# Dual_filter_common_mode_and_differential.net
KiCad netlist of a schematic drawn in EAGLE
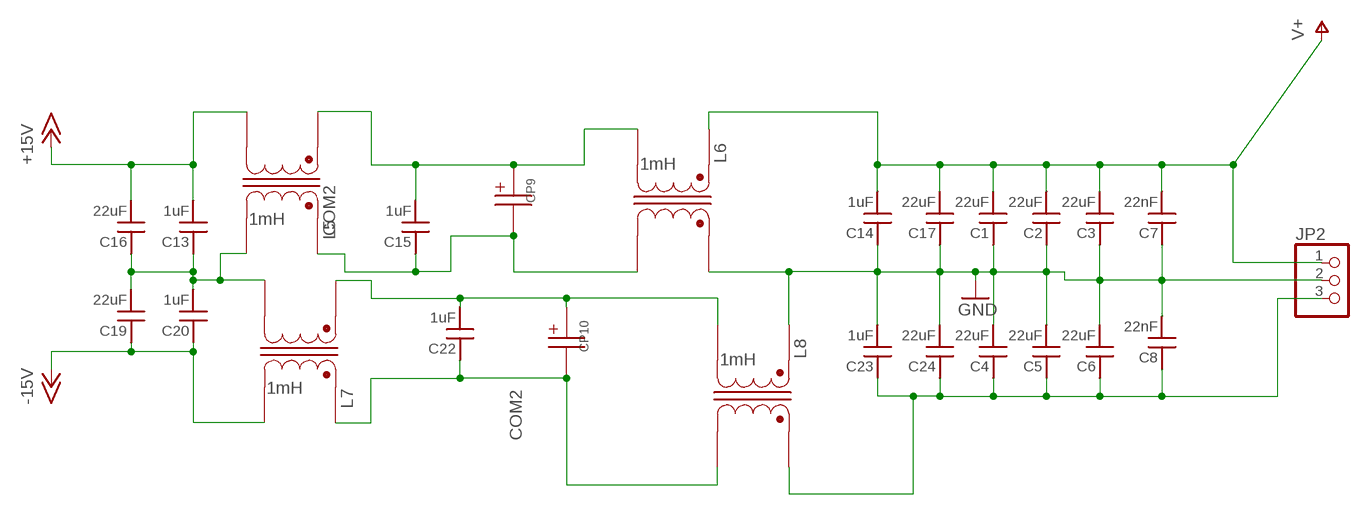
[diagram p0: schematic, sheet 1]

(export (version "E")
  (design (tool "Eeschema 10.0.6"))
  (components
    (comp (ref "C1")
      (value "22uF")
      (footprint "eagle-import:C_MLCC_0805")
      (libsource (lib "eagle-import") (part "C_MLCC_SMDCMLCC_0805"))
    )
    (comp (ref "C2")
      (value "22uF")
      (footprint "eagle-import:C_MLCC_0805")
      (libsource (lib "eagle-import") (part "C_MLCC_SMDCMLCC_0805"))
    )
    (comp (ref "C3")
      (value "22uF")
      (footprint "eagle-import:C_MLCC_0805")
      (libsource (lib "eagle-import") (part "C_MLCC_SMDCMLCC_0805"))
    )
    (comp (ref "C4")
      (value "22uF")
      (footprint "eagle-import:C_MLCC_0805")
      (libsource (lib "eagle-import") (part "C_MLCC_SMDCMLCC_0805"))
    )
    (comp (ref "C5")
      (value "22uF")
      (footprint "eagle-import:C_MLCC_0805")
      (libsource (lib "eagle-import") (part "C_MLCC_SMDCMLCC_0805"))
    )
    (comp (ref "C6")
      (value "22uF")
      (footprint "eagle-import:C_MLCC_0805")
      (libsource (lib "eagle-import") (part "C_MLCC_SMDCMLCC_0805"))
    )
    (comp (ref "C7")
      (value "22nF")
      (footprint "eagle-import:C_MLCC_0306")
      (libsource (lib "eagle-import") (part "C_MLCC_SMDCMLCC_0306"))
    )
    (comp (ref "C8")
      (value "22nF")
      (footprint "eagle-import:C_MLCC_0306")
      (libsource (lib "eagle-import") (part "C_MLCC_SMDCMLCC_0306"))
    )
    (comp (ref "C13")
      (value "1uF")
      (footprint "eagle-import:C_MLCC_0805")
      (libsource (lib "eagle-import") (part "C_MLCC_SMDCMLCC_0805"))
    )
    (comp (ref "C14")
      (value "1uF")
      (footprint "eagle-import:C_MLCC_0805")
      (libsource (lib "eagle-import") (part "C_MLCC_SMDCMLCC_0805"))
    )
    (comp (ref "C15")
      (value "1uF")
      (footprint "eagle-import:C_MLCC_0805")
      (libsource (lib "eagle-import") (part "C_MLCC_SMDCMLCC_0805"))
    )
    (comp (ref "C16")
      (value "22uF")
      (footprint "eagle-import:C_MLCC_0805")
      (libsource (lib "eagle-import") (part "C_MLCC_SMDCMLCC_0805"))
    )
    (comp (ref "C17")
      (value "22uF")
      (footprint "eagle-import:C_MLCC_0805")
      (libsource (lib "eagle-import") (part "C_MLCC_SMDCMLCC_0805"))
    )
    (comp (ref "C19")
      (value "22uF")
      (footprint "eagle-import:C_MLCC_0805")
      (libsource (lib "eagle-import") (part "C_MLCC_SMDCMLCC_0805"))
    )
    (comp (ref "C20")
      (value "1uF")
      (footprint "eagle-import:C_MLCC_0805")
      (libsource (lib "eagle-import") (part "C_MLCC_SMDCMLCC_0805"))
    )
    (comp (ref "C22")
      (value "1uF")
      (footprint "eagle-import:C_MLCC_0805")
      (libsource (lib "eagle-import") (part "C_MLCC_SMDCMLCC_0805"))
    )
    (comp (ref "C23")
      (value "1uF")
      (footprint "eagle-import:C_MLCC_0805")
      (libsource (lib "eagle-import") (part "C_MLCC_SMDCMLCC_0805"))
    )
    (comp (ref "C24")
      (value "22uF")
      (footprint "eagle-import:C_MLCC_0805")
      (libsource (lib "eagle-import") (part "C_MLCC_SMDCMLCC_0805"))
    )
    (comp (ref "CP9")
      (value "CAP-POLPANASONIC_F")
      (footprint "eagle-import:PANASONIC_F")
      (libsource (lib "eagle-import") (part "CAP-POLPANASONIC_F"))
    )
    (comp (ref "CP10")
      (value "CAP-POLPANASONIC_F")
      (footprint "eagle-import:PANASONIC_F")
      (libsource (lib "eagle-import") (part "CAP-POLPANASONIC_F"))
    )
    (comp (ref "JP2")
      (value "PINHD-1X3")
      (footprint "eagle-import:1X03")
      (libsource (lib "eagle-import") (part "PINHD-1X3"))
    )
    (comp (ref "L5")
      (value "1mH")
      (footprint "eagle-import:COILCRAFT_TRANSFORMER_MSD1260")
      (libsource (lib "eagle-import") (part "COILCRAFT_MSD1260"))
    )
    (comp (ref "L6")
      (value "1mH")
      (footprint "eagle-import:COILCRAFT_TRANSFORMER_MSD1260")
      (libsource (lib "eagle-import") (part "COILCRAFT_MSD1260"))
    )
    (comp (ref "L7")
      (value "1mH")
      (footprint "eagle-import:COILCRAFT_TRANSFORMER_MSD1260")
      (libsource (lib "eagle-import") (part "COILCRAFT_MSD1260"))
    )
    (comp (ref "L8")
      (value "1mH")
      (footprint "eagle-import:COILCRAFT_TRANSFORMER_MSD1260")
      (libsource (lib "eagle-import") (part "COILCRAFT_MSD1260"))
    )
  )
  (nets
    (net (code "1") (name "+15V") (class "Default")
      (node (ref "C13") (pin "P$2") (pinfunction "2_P$2") (pintype "passive"))
      (node (ref "C16") (pin "P$2") (pinfunction "2_P$2") (pintype "passive"))
      (node (ref "L5") (pin "P$4") (pinfunction "4_P$4") (pintype "bidirectional"))
    )
    (net (code "2") (name "-15V") (class "Default")
      (node (ref "C19") (pin "P$1") (pinfunction "1_P$1") (pintype "passive"))
      (node (ref "C20") (pin "P$1") (pinfunction "1_P$1") (pintype "passive"))
      (node (ref "L7") (pin "P$3") (pinfunction "3_P$3") (pintype "bidirectional"))
    )
    (net (code "3") (name "/COM2") (class "Default")
      (node (ref "C13") (pin "P$1") (pinfunction "1_P$1") (pintype "passive"))
      (node (ref "C16") (pin "P$1") (pinfunction "1_P$1") (pintype "passive"))
      (node (ref "C19") (pin "P$2") (pinfunction "2_P$2") (pintype "passive"))
      (node (ref "C20") (pin "P$2") (pinfunction "2_P$2") (pintype "passive"))
      (node (ref "L5") (pin "P$3") (pinfunction "3_P$3") (pintype "bidirectional"))
      (node (ref "L7") (pin "P$4") (pinfunction "4_P$4") (pintype "bidirectional"))
    )
    (net (code "4") (name "GND") (class "Default")
      (node (ref "C1") (pin "P$1") (pinfunction "1_P$1") (pintype "passive"))
      (node (ref "C14") (pin "P$1") (pinfunction "1_P$1") (pintype "passive"))
      (node (ref "C17") (pin "P$1") (pinfunction "1_P$1") (pintype "passive"))
      (node (ref "C2") (pin "P$1") (pinfunction "1_P$1") (pintype "passive"))
      (node (ref "C23") (pin "P$2") (pinfunction "2_P$2") (pintype "passive"))
      (node (ref "C24") (pin "P$2") (pinfunction "2_P$2") (pintype "passive"))
      (node (ref "C3") (pin "P$1") (pinfunction "1_P$1") (pintype "passive"))
      (node (ref "C4") (pin "P$2") (pinfunction "2_P$2") (pintype "passive"))
      (node (ref "C5") (pin "P$2") (pinfunction "2_P$2") (pintype "passive"))
      (node (ref "C6") (pin "P$2") (pinfunction "2_P$2") (pintype "passive"))
      (node (ref "C7") (pin "P$1") (pinfunction "1_P$1") (pintype "passive"))
      (node (ref "C8") (pin "P$2") (pinfunction "2_P$2") (pintype "passive"))
      (node (ref "JP2") (pin "2") (pinfunction "2_2") (pintype "passive"))
      (node (ref "L6") (pin "P$2") (pinfunction "2_P$2") (pintype "bidirectional"))
      (node (ref "L8") (pin "P$1") (pinfunction "1_P$1") (pintype "bidirectional"))
    )
    (net (code "5") (name "Net-(C15-1)") (class "Default")
      (node (ref "C15") (pin "P$1") (pinfunction "1_P$1") (pintype "passive"))
      (node (ref "CP9") (pin "-") (pinfunction "P$2_-") (pintype "passive"))
      (node (ref "L5") (pin "P$1") (pinfunction "1_P$1") (pintype "bidirectional"))
      (node (ref "L6") (pin "P$4") (pinfunction "4_P$4") (pintype "bidirectional"))
    )
    (net (code "6") (name "Net-(C15-2)") (class "Default")
      (node (ref "C15") (pin "P$2") (pinfunction "2_P$2") (pintype "passive"))
      (node (ref "CP9") (pin "+") (pinfunction "P$1_+") (pintype "passive"))
      (node (ref "L5") (pin "P$2") (pinfunction "2_P$2") (pintype "bidirectional"))
      (node (ref "L6") (pin "P$3") (pinfunction "3_P$3") (pintype "bidirectional"))
    )
    (net (code "7") (name "Net-(C22-1)") (class "Default")
      (node (ref "C22") (pin "P$1") (pinfunction "1_P$1") (pintype "passive"))
      (node (ref "CP10") (pin "-") (pinfunction "P$2_-") (pintype "passive"))
      (node (ref "L7") (pin "P$1") (pinfunction "1_P$1") (pintype "bidirectional"))
      (node (ref "L8") (pin "P$4") (pinfunction "4_P$4") (pintype "bidirectional"))
    )
    (net (code "8") (name "Net-(C22-2)") (class "Default")
      (node (ref "C22") (pin "P$2") (pinfunction "2_P$2") (pintype "passive"))
      (node (ref "CP10") (pin "+") (pinfunction "P$1_+") (pintype "passive"))
      (node (ref "L7") (pin "P$2") (pinfunction "2_P$2") (pintype "bidirectional"))
      (node (ref "L8") (pin "P$3") (pinfunction "3_P$3") (pintype "bidirectional"))
    )
    (net (code "9") (name "Net-(C23-1)") (class "Default")
      (node (ref "C23") (pin "P$1") (pinfunction "1_P$1") (pintype "passive"))
      (node (ref "C24") (pin "P$1") (pinfunction "1_P$1") (pintype "passive"))
      (node (ref "C4") (pin "P$1") (pinfunction "1_P$1") (pintype "passive"))
      (node (ref "C5") (pin "P$1") (pinfunction "1_P$1") (pintype "passive"))
      (node (ref "C6") (pin "P$1") (pinfunction "1_P$1") (pintype "passive"))
      (node (ref "C8") (pin "P$1") (pinfunction "1_P$1") (pintype "passive"))
      (node (ref "JP2") (pin "3") (pinfunction "3_3") (pintype "passive"))
      (node (ref "L8") (pin "P$2") (pinfunction "2_P$2") (pintype "bidirectional"))
    )
    (net (code "10") (name "V+") (class "Default")
      (node (ref "C1") (pin "P$2") (pinfunction "2_P$2") (pintype "passive"))
      (node (ref "C14") (pin "P$2") (pinfunction "2_P$2") (pintype "passive"))
      (node (ref "C17") (pin "P$2") (pinfunction "2_P$2") (pintype "passive"))
      (node (ref "C2") (pin "P$2") (pinfunction "2_P$2") (pintype "passive"))
      (node (ref "C3") (pin "P$2") (pinfunction "2_P$2") (pintype "passive"))
      (node (ref "C7") (pin "P$2") (pinfunction "2_P$2") (pintype "passive"))
      (node (ref "JP2") (pin "1") (pinfunction "1_1") (pintype "passive"))
      (node (ref "L6") (pin "P$1") (pinfunction "1_P$1") (pintype "bidirectional"))
    )
  )
)
